# MRCS-Adapter-CRMI8-RJ45-Inverting.net
KiCad netlist of a schematic drawn in EAGLE
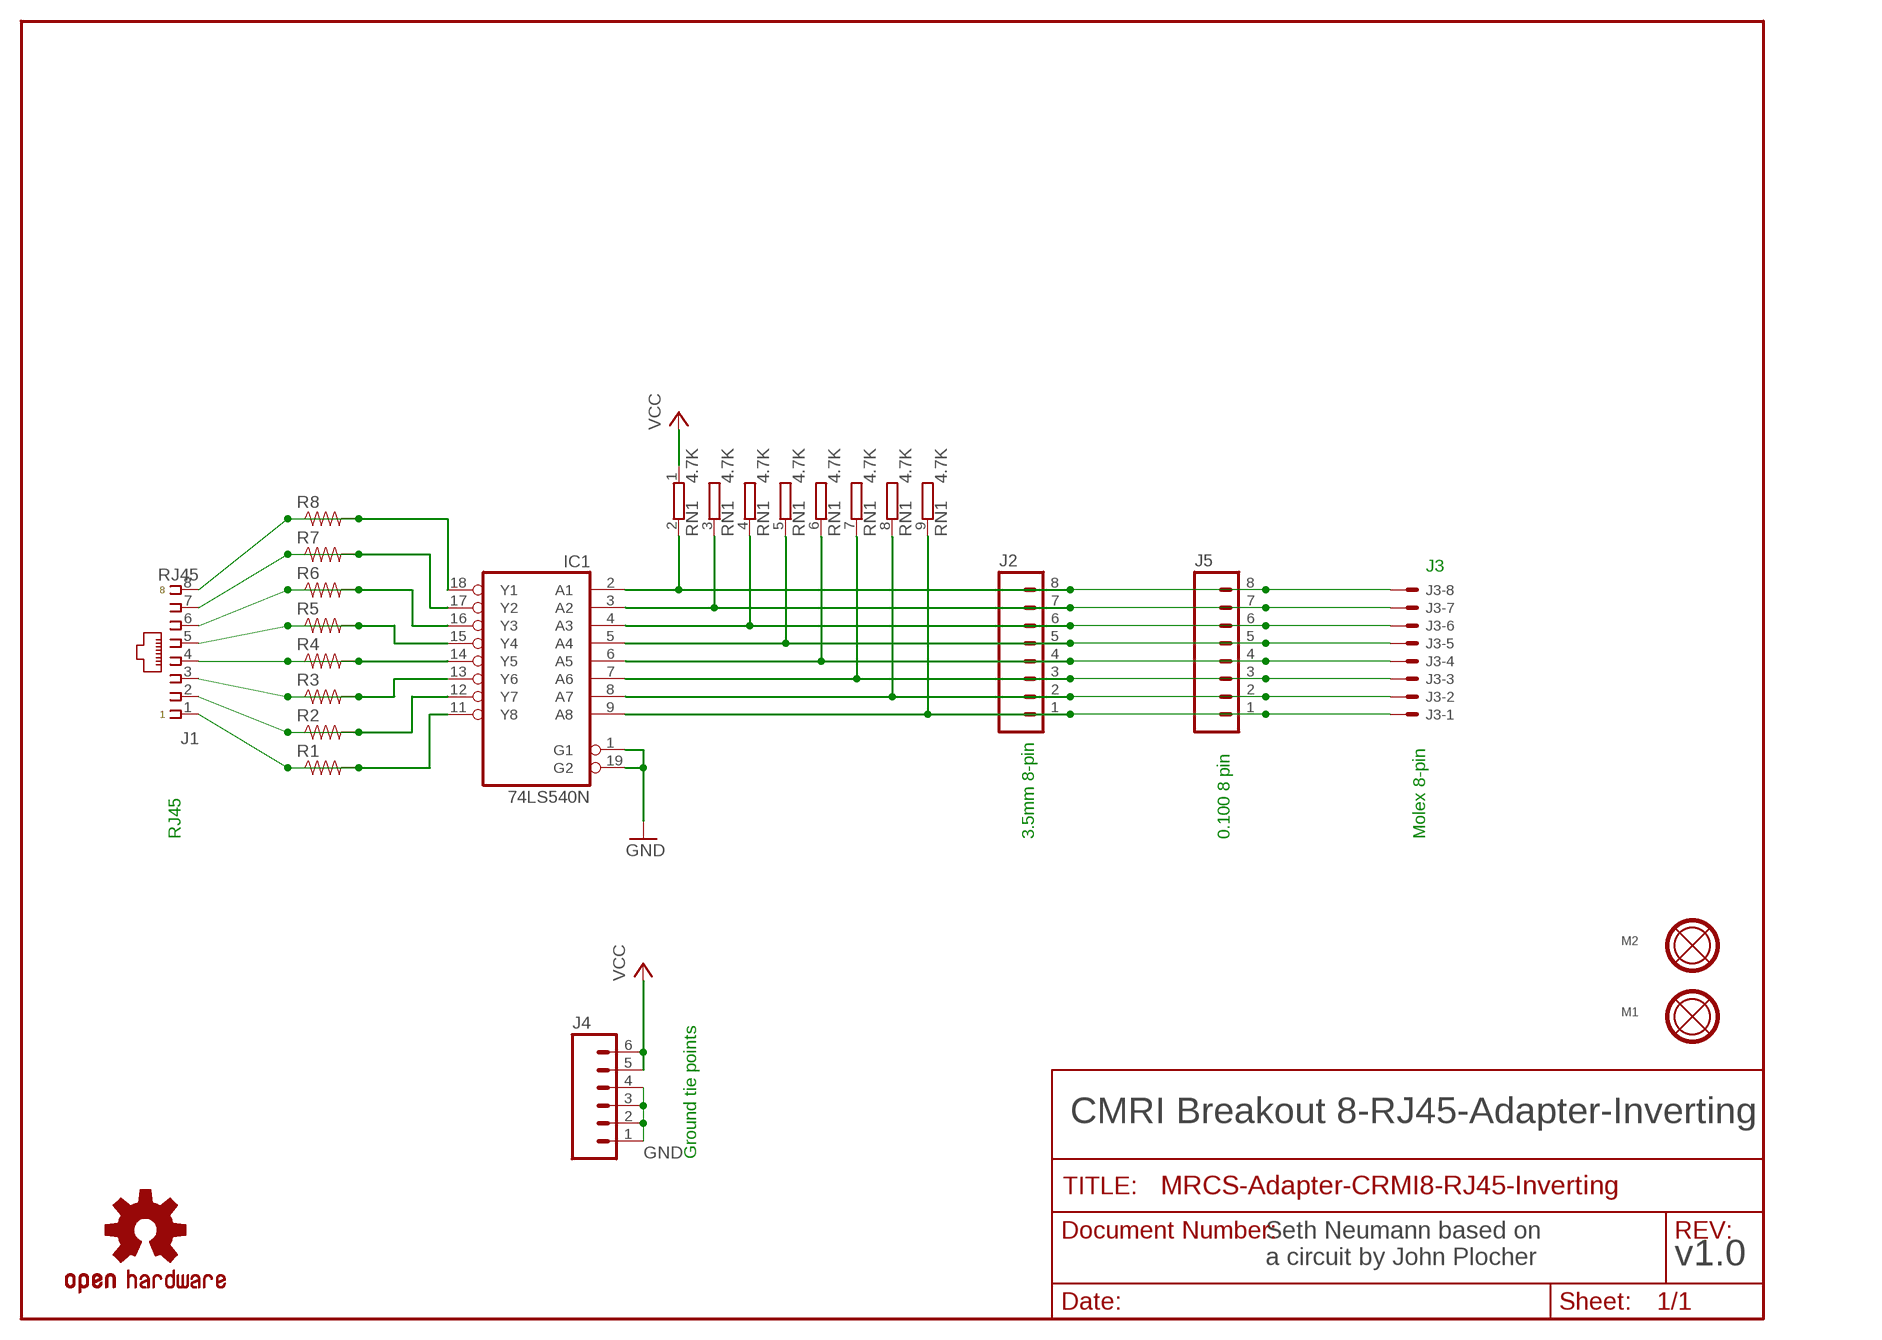
[diagram p0: schematic, sheet 1]

(export (version "E")
  (design (tool "Eeschema 10.0.6"))
  (components
    (comp (ref "IC1")
      (value "74LS540N")
      (footprint "eagle-import:DIL20")
      (libsource (lib "eagle-import") (part "74540NLS"))
    )
    (comp (ref "J1")
      (value "RJ45")
      (footprint "eagle-import:RJ45-NO-SHIELD")
      (libsource (lib "eagle-import") (part "CONNECTOR-RJ45-FRONT"))
    )
    (comp (ref "J2")
      (value "CONNECTOR-M083.5MM-8")
      (footprint "eagle-import:SCREWTERMINAL-3.5MM-8")
      (libsource (lib "eagle-import") (part "CONNECTOR-M083.5MM-8"))
    )
    (comp (ref "J3")
      (value "KK-156-8F")
      (footprint "eagle-import:KK-156-8-F")
      (libsource (lib "eagle-import") (part "KK-156-8F"))
    )
    (comp (ref "J4")
      (value "CONNECTOR-M06LOCK")
      (footprint "eagle-import:1X06_LOCK")
      (libsource (lib "eagle-import") (part "CONNECTOR-M06LOCK"))
    )
    (comp (ref "J5")
      (value "CONNECTOR-M08LOCK")
      (footprint "eagle-import:1X08_LOCK")
      (libsource (lib "eagle-import") (part "CONNECTOR-M08LOCK"))
    )
    (comp (ref "M1")
      (value "MOUNTINGHOLE")
      (footprint "eagle-import:MOUNTINGHOLE")
      (libsource (lib "eagle-import") (part "MOUNTINGHOLE"))
    )
    (comp (ref "M2")
      (value "MOUNTINGHOLE")
      (footprint "eagle-import:MOUNTINGHOLE")
      (libsource (lib "eagle-import") (part "MOUNTINGHOLE"))
    )
    (comp (ref "R1")
      (value "RPTH04")
      (footprint "eagle-import:AXIAL-0.4-RES")
      (libsource (lib "eagle-import") (part "RPTH04"))
    )
    (comp (ref "R2")
      (value "RPTH04")
      (footprint "eagle-import:AXIAL-0.4-RES")
      (libsource (lib "eagle-import") (part "RPTH04"))
    )
    (comp (ref "R3")
      (value "RPTH04")
      (footprint "eagle-import:AXIAL-0.4-RES")
      (libsource (lib "eagle-import") (part "RPTH04"))
    )
    (comp (ref "R4")
      (value "RPTH04")
      (footprint "eagle-import:AXIAL-0.4-RES")
      (libsource (lib "eagle-import") (part "RPTH04"))
    )
    (comp (ref "R5")
      (value "RPTH04")
      (footprint "eagle-import:AXIAL-0.4-RES")
      (libsource (lib "eagle-import") (part "RPTH04"))
    )
    (comp (ref "R6")
      (value "RPTH04")
      (footprint "eagle-import:AXIAL-0.4-RES")
      (libsource (lib "eagle-import") (part "RPTH04"))
    )
    (comp (ref "R7")
      (value "RPTH04")
      (footprint "eagle-import:AXIAL-0.4-RES")
      (libsource (lib "eagle-import") (part "RPTH04"))
    )
    (comp (ref "R8")
      (value "RPTH04")
      (footprint "eagle-import:AXIAL-0.4-RES")
      (libsource (lib "eagle-import") (part "RPTH04"))
    )
    (comp (ref "RN1")
      (value "4.7K")
      (footprint "eagle-import:SIL9")
      (libsource (lib "eagle-import") (part "GE08RP"))
    )
    (comp (ref "U$1")
      (value "DOC-OSHW-LOGO-L")
      (footprint "eagle-import:OSHW-LOGO-L")
      (libsource (lib "eagle-import") (part "DOC-OSHW-LOGO-L"))
    )
  )
  (nets
    (net (code "1") (name "GND") (class "Default")
      (node (ref "IC1") (pin "1") (pinfunction "G1_1") (pintype "input"))
      (node (ref "IC1") (pin "19") (pinfunction "G2_19") (pintype "input"))
      (node (ref "J4") (pin "1") (pinfunction "1_1") (pintype "passive"))
      (node (ref "J4") (pin "2") (pinfunction "2_2") (pintype "passive"))
      (node (ref "J4") (pin "3") (pinfunction "3_3") (pintype "passive"))
      (node (ref "J4") (pin "4") (pinfunction "4_4") (pintype "passive"))
    )
    (net (code "2") (name "Net-(IC1A-A1)") (class "Default")
      (node (ref "IC1") (pin "2") (pinfunction "A1_2") (pintype "input"))
      (node (ref "J2") (pin "8") (pinfunction "8_8") (pintype "passive"))
      (node (ref "J3") (pin "8") (pinfunction "S_8") (pintype "passive"))
      (node (ref "J5") (pin "8") (pinfunction "8_8") (pintype "passive"))
      (node (ref "RN1") (pin "2") (pinfunction "2_2") (pintype "passive"))
    )
    (net (code "3") (name "Net-(IC1A-A2)") (class "Default")
      (node (ref "IC1") (pin "3") (pinfunction "A2_3") (pintype "input"))
      (node (ref "J2") (pin "7") (pinfunction "7_7") (pintype "passive"))
      (node (ref "J3") (pin "7") (pinfunction "S_7") (pintype "passive"))
      (node (ref "J5") (pin "7") (pinfunction "7_7") (pintype "passive"))
      (node (ref "RN1") (pin "3") (pinfunction "2_3") (pintype "passive"))
    )
    (net (code "4") (name "Net-(IC1A-A3)") (class "Default")
      (node (ref "IC1") (pin "4") (pinfunction "A3_4") (pintype "input"))
      (node (ref "J2") (pin "6") (pinfunction "6_6") (pintype "passive"))
      (node (ref "J3") (pin "6") (pinfunction "S_6") (pintype "passive"))
      (node (ref "J5") (pin "6") (pinfunction "6_6") (pintype "passive"))
      (node (ref "RN1") (pin "4") (pinfunction "2_4") (pintype "passive"))
    )
    (net (code "5") (name "Net-(IC1A-A4)") (class "Default")
      (node (ref "IC1") (pin "5") (pinfunction "A4_5") (pintype "input"))
      (node (ref "J2") (pin "5") (pinfunction "5_5") (pintype "passive"))
      (node (ref "J3") (pin "5") (pinfunction "S_5") (pintype "passive"))
      (node (ref "J5") (pin "5") (pinfunction "5_5") (pintype "passive"))
      (node (ref "RN1") (pin "5") (pinfunction "2_5") (pintype "passive"))
    )
    (net (code "6") (name "Net-(IC1A-A5)") (class "Default")
      (node (ref "IC1") (pin "6") (pinfunction "A5_6") (pintype "input"))
      (node (ref "J2") (pin "4") (pinfunction "4_4") (pintype "passive"))
      (node (ref "J3") (pin "4") (pinfunction "S_4") (pintype "passive"))
      (node (ref "J5") (pin "4") (pinfunction "4_4") (pintype "passive"))
      (node (ref "RN1") (pin "6") (pinfunction "2_6") (pintype "passive"))
    )
    (net (code "7") (name "Net-(IC1A-A6)") (class "Default")
      (node (ref "IC1") (pin "7") (pinfunction "A6_7") (pintype "input"))
      (node (ref "J2") (pin "3") (pinfunction "3_3") (pintype "passive"))
      (node (ref "J3") (pin "3") (pinfunction "S_3") (pintype "passive"))
      (node (ref "J5") (pin "3") (pinfunction "3_3") (pintype "passive"))
      (node (ref "RN1") (pin "7") (pinfunction "2_7") (pintype "passive"))
    )
    (net (code "8") (name "Net-(IC1A-A7)") (class "Default")
      (node (ref "IC1") (pin "8") (pinfunction "A7_8") (pintype "input"))
      (node (ref "J2") (pin "2") (pinfunction "2_2") (pintype "passive"))
      (node (ref "J3") (pin "2") (pinfunction "S_2") (pintype "passive"))
      (node (ref "J5") (pin "2") (pinfunction "2_2") (pintype "passive"))
      (node (ref "RN1") (pin "8") (pinfunction "2_8") (pintype "passive"))
    )
    (net (code "9") (name "Net-(IC1A-A8)") (class "Default")
      (node (ref "IC1") (pin "9") (pinfunction "A8_9") (pintype "input"))
      (node (ref "J2") (pin "1") (pinfunction "1_1") (pintype "passive"))
      (node (ref "J3") (pin "1") (pinfunction "S_1") (pintype "passive"))
      (node (ref "J5") (pin "1") (pinfunction "1_1") (pintype "passive"))
      (node (ref "RN1") (pin "9") (pinfunction "2_9") (pintype "passive"))
    )
    (net (code "10") (name "Net-(IC1A-Y1)") (class "Default")
      (node (ref "IC1") (pin "18") (pinfunction "Y1_18") (pintype "tri_state"))
      (node (ref "J1") (pin "8") (pinfunction "8_8") (pintype "passive"))
      (node (ref "R8") (pin "P$1") (pinfunction "1_P$1") (pintype "passive"))
      (node (ref "R8") (pin "P$2") (pinfunction "2_P$2") (pintype "passive"))
    )
    (net (code "11") (name "Net-(IC1A-Y2)") (class "Default")
      (node (ref "IC1") (pin "17") (pinfunction "Y2_17") (pintype "tri_state"))
      (node (ref "J1") (pin "7") (pinfunction "7_7") (pintype "passive"))
      (node (ref "R7") (pin "P$1") (pinfunction "1_P$1") (pintype "passive"))
      (node (ref "R7") (pin "P$2") (pinfunction "2_P$2") (pintype "passive"))
    )
    (net (code "12") (name "Net-(IC1A-Y3)") (class "Default")
      (node (ref "IC1") (pin "16") (pinfunction "Y3_16") (pintype "tri_state"))
      (node (ref "J1") (pin "6") (pinfunction "6_6") (pintype "passive"))
      (node (ref "R6") (pin "P$1") (pinfunction "1_P$1") (pintype "passive"))
      (node (ref "R6") (pin "P$2") (pinfunction "2_P$2") (pintype "passive"))
    )
    (net (code "13") (name "Net-(IC1A-Y4)") (class "Default")
      (node (ref "IC1") (pin "15") (pinfunction "Y4_15") (pintype "tri_state"))
      (node (ref "J1") (pin "5") (pinfunction "5_5") (pintype "passive"))
      (node (ref "R5") (pin "P$1") (pinfunction "1_P$1") (pintype "passive"))
      (node (ref "R5") (pin "P$2") (pinfunction "2_P$2") (pintype "passive"))
    )
    (net (code "14") (name "Net-(IC1A-Y5)") (class "Default")
      (node (ref "IC1") (pin "14") (pinfunction "Y5_14") (pintype "tri_state"))
      (node (ref "J1") (pin "4") (pinfunction "4_4") (pintype "passive"))
      (node (ref "R4") (pin "P$1") (pinfunction "1_P$1") (pintype "passive"))
      (node (ref "R4") (pin "P$2") (pinfunction "2_P$2") (pintype "passive"))
    )
    (net (code "15") (name "Net-(IC1A-Y6)") (class "Default")
      (node (ref "IC1") (pin "13") (pinfunction "Y6_13") (pintype "tri_state"))
      (node (ref "J1") (pin "3") (pinfunction "3_3") (pintype "passive"))
      (node (ref "R3") (pin "P$1") (pinfunction "1_P$1") (pintype "passive"))
      (node (ref "R3") (pin "P$2") (pinfunction "2_P$2") (pintype "passive"))
    )
    (net (code "16") (name "Net-(IC1A-Y7)") (class "Default")
      (node (ref "IC1") (pin "12") (pinfunction "Y7_12") (pintype "tri_state"))
      (node (ref "J1") (pin "2") (pinfunction "2_2") (pintype "passive"))
      (node (ref "R2") (pin "P$1") (pinfunction "1_P$1") (pintype "passive"))
      (node (ref "R2") (pin "P$2") (pinfunction "2_P$2") (pintype "passive"))
    )
    (net (code "17") (name "Net-(IC1A-Y8)") (class "Default")
      (node (ref "IC1") (pin "11") (pinfunction "Y8_11") (pintype "tri_state"))
      (node (ref "J1") (pin "1") (pinfunction "1_1") (pintype "passive"))
      (node (ref "R1") (pin "P$1") (pinfunction "1_P$1") (pintype "passive"))
      (node (ref "R1") (pin "P$2") (pinfunction "2_P$2") (pintype "passive"))
    )
    (net (code "18") (name "VCC") (class "Default")
      (node (ref "J4") (pin "5") (pinfunction "5_5") (pintype "passive"))
      (node (ref "J4") (pin "6") (pinfunction "6_6") (pintype "passive"))
      (node (ref "RN1") (pin "1") (pinfunction "1_1") (pintype "passive"))
    )
  )
)
